# nfcsch.net
KiCad netlist of a schematic drawn in EasyEDA
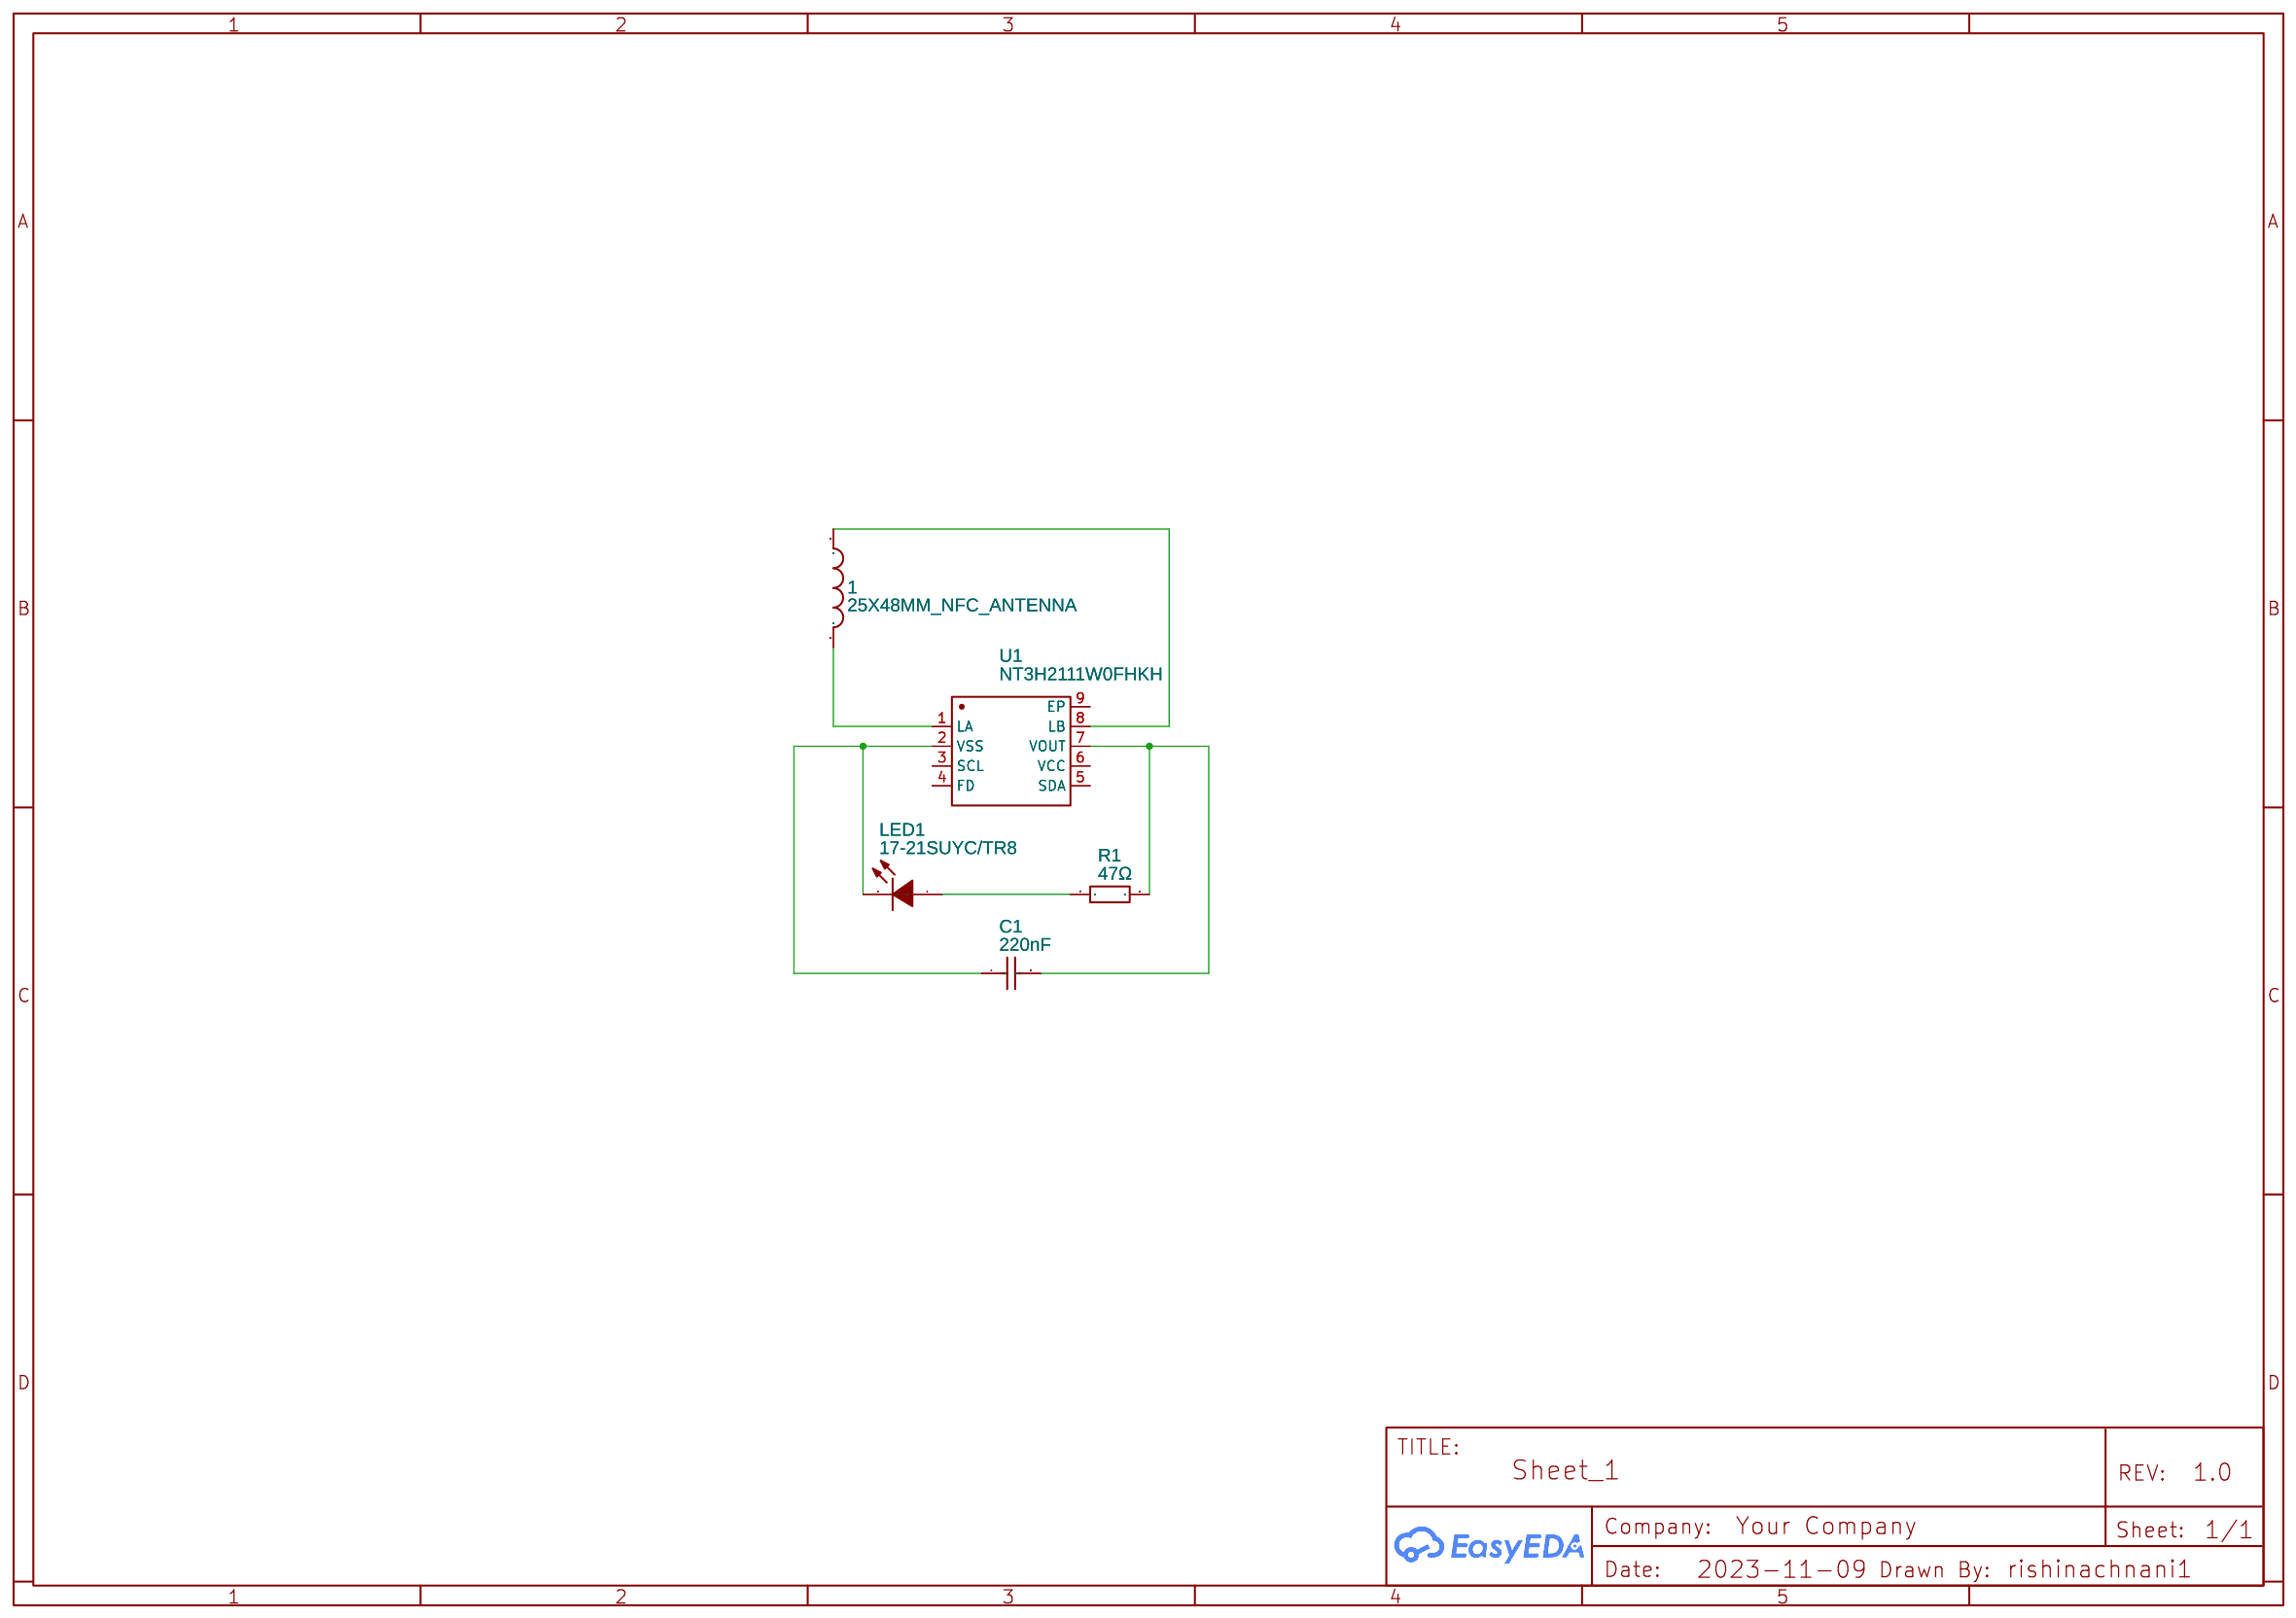
[diagram p0: schematic sheet]

(export (version "E")
  (design (tool "Eeschema 10.0.6"))
  (components
    (comp (ref "1") (value "25X48MM_NFC_ANTENNA") (libsource (lib "") (part "25X48MM_NFC_ANTENNA")))
    (comp (ref "C1")
      (value "220nF")
      (fields
        (field (name "Manufacturer Part") "CL10B224KA8NNNC")
        (field (name "Manufacturer") "SAMSUNG(三星)")
      )
      (libsource (lib "") (part "CL10B224KA8NNNC"))
    )
    (comp (ref "LED1")
      (value "17-21SUYC/TR8")
      (fields (field (name "Manufacturer Part") "KT-0805黄灯") (field (name "Manufacturer") "KENTO"))
      (libsource (lib "") (part "17-21SUYC/TR8"))
    )
    (comp (ref "R1")
      (value "47Ω")
      (fields
        (field (name "Manufacturer Part") "0603WAF470JT5E")
        (field (name "Manufacturer") "UNI-ROYAL(厚声)")
      )
      (libsource (lib "") (part "0603WAF470JT5E"))
    )
    (comp (ref "U1")
      (value "NT3H2111W0FHKH")
      (fields (field (name "Manufacturer") "NXP(恩智浦)"))
      (libsource (lib "") (part "NT3H2111W0FHKH"))
    )
  )
  (nets
    (net (code "1") (name "Net-(LED1-+)") (class "Default")
      (node (ref "LED1") (pin "1") (pinfunction "+_1") (pintype "unspecified"))
      (node (ref "R1") (pin "1") (pinfunction "1_1") (pintype "input"))
    )
    (net (code "2") (name "Net-(LED1--)") (class "Default")
      (node (ref "C1") (pin "1") (pinfunction "1_1") (pintype "input"))
      (node (ref "LED1") (pin "2") (pinfunction "-_2") (pintype "unspecified"))
      (node (ref "U1") (pin "2") (pinfunction "VSS_2") (pintype "unspecified"))
    )
    (net (code "3") (name "Net-(U1-LA)") (class "Default")
      (node (ref "1") (pin "P$2") (pinfunction "P$2_P$2") (pintype "bidirectional"))
      (node (ref "U1") (pin "1") (pinfunction "LA_1") (pintype "unspecified"))
    )
    (net (code "4") (name "Net-(U1-LB)") (class "Default")
      (node (ref "1") (pin "P$1") (pinfunction "P$1_P$1") (pintype "bidirectional"))
      (node (ref "U1") (pin "8") (pinfunction "LB_8") (pintype "unspecified"))
    )
    (net (code "5") (name "Net-(U1-VOUT)") (class "Default")
      (node (ref "C1") (pin "2") (pinfunction "2_2") (pintype "input"))
      (node (ref "R1") (pin "2") (pinfunction "2_2") (pintype "input"))
      (node (ref "U1") (pin "7") (pinfunction "VOUT_7") (pintype "unspecified"))
    )
    (net (code "6") (name "unconnected-(U1-EP-Pad9)") (class "Default")
      (node (ref "U1") (pin "9") (pinfunction "EP_9") (pintype "unspecified"))
    )
    (net (code "7") (name "unconnected-(U1-FD-Pad4)") (class "Default")
      (node (ref "U1") (pin "4") (pinfunction "FD_4") (pintype "unspecified"))
    )
    (net (code "8") (name "unconnected-(U1-SCL-Pad3)") (class "Default")
      (node (ref "U1") (pin "3") (pinfunction "SCL_3") (pintype "unspecified"))
    )
    (net (code "9") (name "unconnected-(U1-SDA-Pad5)") (class "Default")
      (node (ref "U1") (pin "5") (pinfunction "SDA_5") (pintype "unspecified"))
    )
    (net (code "10") (name "unconnected-(U1-VCC-Pad6)") (class "Default")
      (node (ref "U1") (pin "6") (pinfunction "VCC_6") (pintype "unspecified"))
    )
  )
)
